# ProPrj_Book_Nook_Lamp_2026-02-12.net
KiCad netlist of a schematic drawn in EasyEDA Pro
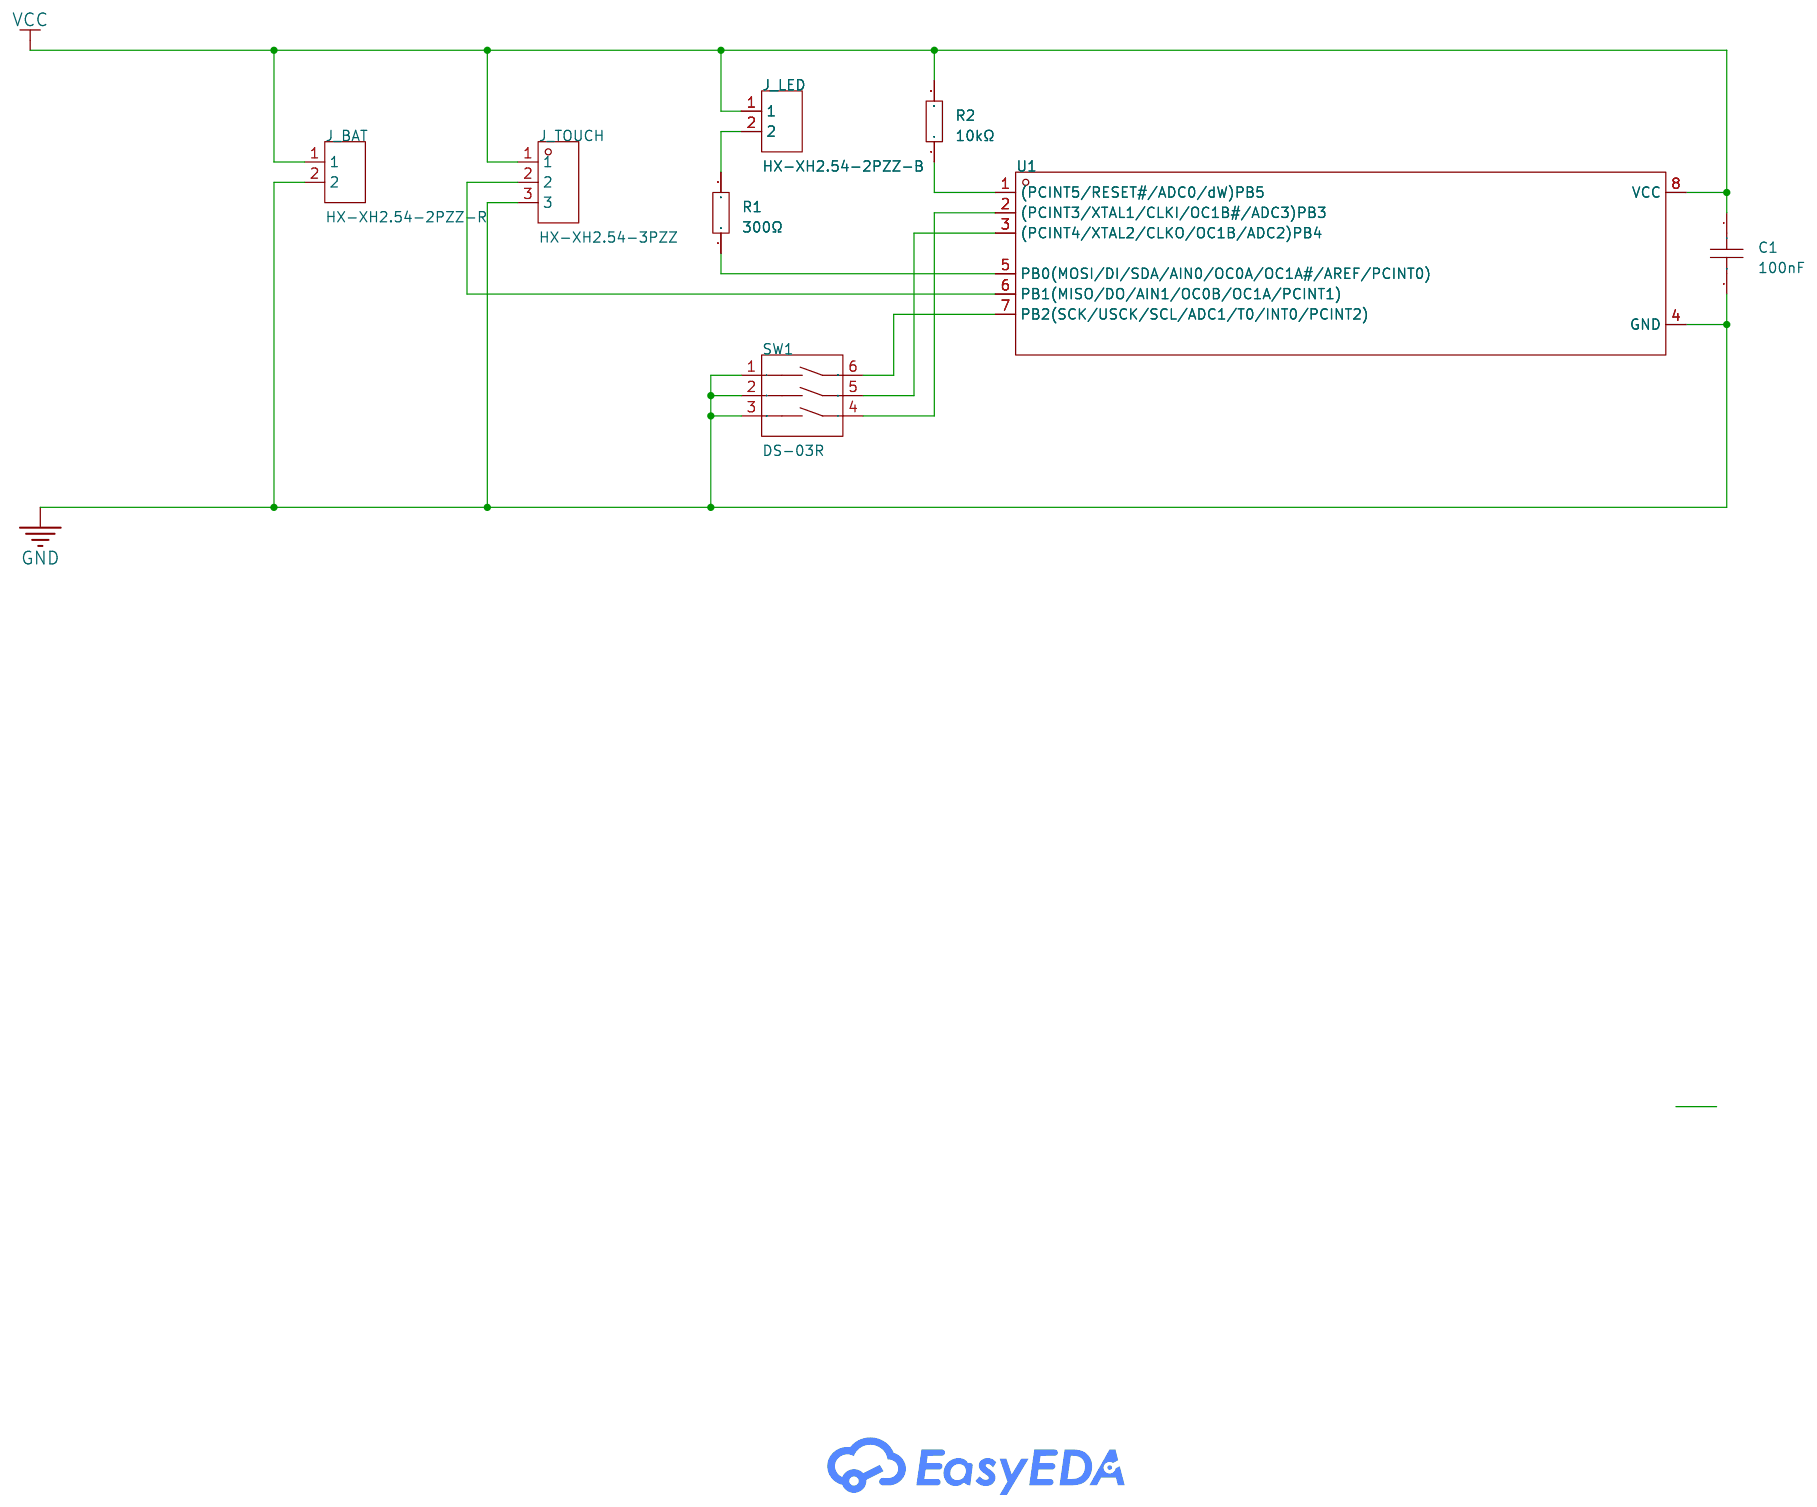
[diagram p0: schematic sheet]

(export (version "E")
  (design (tool "Eeschema 10.0.6"))
  (components
    (comp (ref "C1")
      (value "100nF")
      (footprint "easyedapro:CAP-TH_L5.5-W2.5-P5.00-D0.50-S2.0")
      (fields
        (field (name "Manufacturer Part") "CC1H104ZA1ED3F5P1100")
        (field (name "Manufacturer") "Dersonic(德尔创)")
      )
      (libsource (lib "easyedapro") (part "CC1H104ZC1FD3F5O1100"))
    )
    (comp (ref "J_BAT")
      (value "HX-XH2.54-2PZZ-R")
      (footprint "easyedapro:HDR-TH_2P-P2.54-V-M-1")
      (fields (field (name "Manufacturer") "hanxia(韩下)"))
      (libsource (lib "easyedapro") (part "HDR1X2"))
    )
    (comp (ref "J_LED")
      (value "HX-XH2.54-2PZZ-B")
      (footprint "easyedapro:HDR-TH_2P-P2.54-V-M-1")
      (fields (field (name "Manufacturer") "hanxia(韩下)"))
      (libsource (lib "easyedapro") (part "HDR1X2"))
    )
    (comp (ref "J_TOUCH")
      (value "HX-XH2.54-3PZZ")
      (footprint "easyedapro:CONN-TH_3P-P2.50_XH-3A-1")
      (fields (field (name "Manufacturer") "hanxia(韩下)"))
      (libsource (lib "easyedapro") (part "HDR1X3-2.54"))
    )
    (comp (ref "R1")
      (value "300Ω")
      (footprint "easyedapro:R0603")
      (fields (field (name "Manufacturer Part") "MF1/4W-300Ω±1%T52") (field (name "Manufacturer") "华星机电"))
      (libsource (lib "easyedapro") (part "Res"))
    )
    (comp (ref "R2")
      (value "10kΩ")
      (footprint "easyedapro:R0603")
      (fields (field (name "Manufacturer Part") "MF1/4W-10K±1%-ST26") (field (name "Manufacturer") "VO(翔胜)"))
      (libsource (lib "easyedapro") (part "Res"))
    )
    (comp (ref "SW1")
      (value "DS-03R")
      (footprint "easyedapro:SW-SMD_DSHP-03")
      (description "Type:Slide, Rocked Circuit:SPST Number of Positions:3 Termination Style:PC Pin Lead Pitch:2.54mm")
      (fields (field (name "Manufacturer") "HanElectricity(瀚源)"))
      (libsource (lib "easyedapro") (part "DSHP-03"))
    )
    (comp (ref "U1")
      (value "ATTINY85-20PU")
      (footprint "easyedapro:PDIP-8_L9.3-W6.4-P2.54-LS7.9-BL-1")
      (fields (field (name "Manufacturer") "MICROCHIP(美国微芯)"))
      (libsource (lib "easyedapro") (part "ATTINY85-20PU"))
    )
  )
  (nets
    (net (code "1") (name "GND") (class "Default")
      (node (ref "C1") (pin "2") (pinfunction "2_2") (pintype "unspecified"))
      (node (ref "J_BAT") (pin "2") (pinfunction "2_2") (pintype "unspecified"))
      (node (ref "J_TOUCH") (pin "3") (pinfunction "3_3") (pintype "unspecified"))
      (node (ref "SW1") (pin "1") (pinfunction "1_1") (pintype "unspecified"))
      (node (ref "SW1") (pin "2") (pinfunction "2_2") (pintype "unspecified"))
      (node (ref "SW1") (pin "3") (pinfunction "3_3") (pintype "unspecified"))
      (node (ref "U1") (pin "4") (pinfunction "GND_4") (pintype "unspecified"))
    )
    (net (code "2") (name "Net-(J_LED-Pad2)") (class "Default")
      (node (ref "J_LED") (pin "2") (pinfunction "2_2") (pintype "unspecified"))
      (node (ref "R1") (pin "2") (pinfunction "2_2") (pintype "input"))
    )
    (net (code "3") (name "Net-(U1-(PCINT3{slash}XTAL1{slash}CLKI{slash}OC1B#{slash}ADC3)PB3)") (class "Default")
      (node (ref "SW1") (pin "4") (pinfunction "4_4") (pintype "unspecified"))
      (node (ref "U1") (pin "2") (pinfunction "(PCINT3/XTAL1/CLKI/OC1B#/ADC3)PB3_2") (pintype "unspecified"))
    )
    (net (code "4") (name "Net-(U1-(PCINT4{slash}XTAL2{slash}CLKO{slash}OC1B{slash}ADC2)PB4)") (class "Default")
      (node (ref "SW1") (pin "5") (pinfunction "5_5") (pintype "unspecified"))
      (node (ref "U1") (pin "3") (pinfunction "(PCINT4/XTAL2/CLKO/OC1B/ADC2)PB4_3") (pintype "unspecified"))
    )
    (net (code "5") (name "Net-(U1-(PCINT5{slash}RESET#{slash}ADC0{slash}dW)PB5)") (class "Default")
      (node (ref "R2") (pin "1") (pinfunction "1_1") (pintype "input"))
      (node (ref "U1") (pin "1") (pinfunction "(PCINT5/RESET#/ADC0/dW)PB5_1") (pintype "unspecified"))
    )
    (net (code "6") (name "Net-(U1-PB0(MOSI{slash}DI{slash}SDA{slash}AIN0{slash}OC0A{slash}OC1A#{slash}AREF{slash}PCINT0))") (class "Default")
      (node (ref "R1") (pin "1") (pinfunction "1_1") (pintype "input"))
      (node (ref "U1") (pin "5") (pinfunction "PB0(MOSI/DI/SDA/AIN0/OC0A/OC1A#/AREF/PCINT0)_5") (pintype "unspecified"))
    )
    (net (code "7") (name "Net-(U1-PB1(MISO{slash}DO{slash}AIN1{slash}OC0B{slash}OC1A{slash}PCINT1))") (class "Default")
      (node (ref "J_TOUCH") (pin "2") (pinfunction "2_2") (pintype "unspecified"))
      (node (ref "U1") (pin "6") (pinfunction "PB1(MISO/DO/AIN1/OC0B/OC1A/PCINT1)_6") (pintype "unspecified"))
    )
    (net (code "8") (name "Net-(U1-PB2(SCK{slash}USCK{slash}SCL{slash}ADC1{slash}T0{slash}INT0{slash}PCINT2))") (class "Default")
      (node (ref "SW1") (pin "6") (pinfunction "6_6") (pintype "unspecified"))
      (node (ref "U1") (pin "7") (pinfunction "PB2(SCK/USCK/SCL/ADC1/T0/INT0/PCINT2)_7") (pintype "unspecified"))
    )
    (net (code "9") (name "VCC") (class "Default")
      (node (ref "C1") (pin "1") (pinfunction "1_1") (pintype "unspecified"))
      (node (ref "J_BAT") (pin "1") (pinfunction "1_1") (pintype "unspecified"))
      (node (ref "J_LED") (pin "1") (pinfunction "1_1") (pintype "unspecified"))
      (node (ref "J_TOUCH") (pin "1") (pinfunction "1_1") (pintype "unspecified"))
      (node (ref "R2") (pin "2") (pinfunction "2_2") (pintype "input"))
      (node (ref "U1") (pin "8") (pinfunction "VCC_8") (pintype "unspecified"))
    )
  )
)
